# SCH.net
KiCad netlist of a schematic drawn in EasyEDA
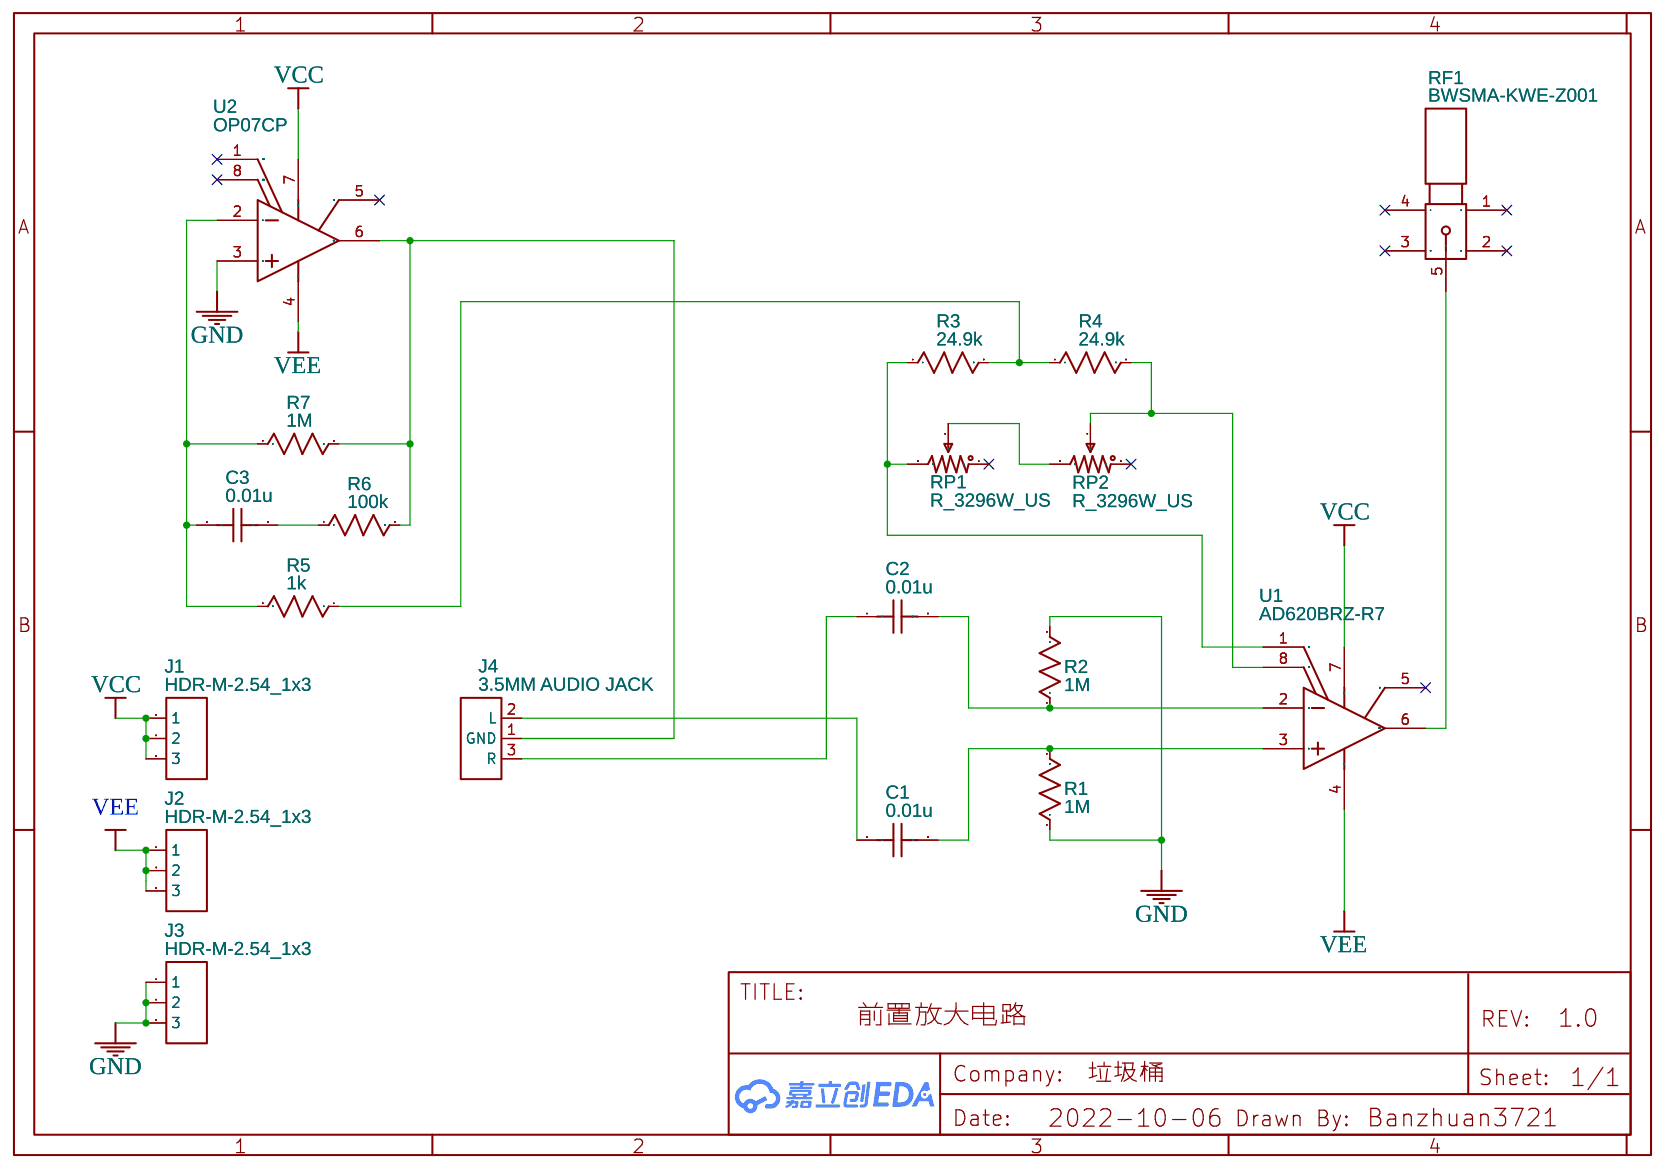
[diagram p0: schematic sheet]

(export (version "E")
  (design (tool "Eeschema 10.0.6"))
  (components
    (comp (ref "C1") (value "0.01u") (libsource (lib "") (part "C_RAD-0.2_US")))
    (comp (ref "C2") (value "0.01u") (libsource (lib "") (part "C_RAD-0.2_US")))
    (comp (ref "C3") (value "0.01u") (libsource (lib "") (part "C_RAD-0.2_US")))
    (comp (ref "J1")
      (value "HDR-M-2.54_1x3")
      (fields (field (name "BOM_Supplier Part") "C180248"))
      (libsource (lib "") (part "HDR-M-2.54_1x3"))
    )
    (comp (ref "J2")
      (value "HDR-M-2.54_1x3")
      (fields (field (name "BOM_Supplier Part") "C180248"))
      (libsource (lib "") (part "HDR-M-2.54_1x3"))
    )
    (comp (ref "J3")
      (value "HDR-M-2.54_1x3")
      (fields (field (name "BOM_Supplier Part") "C180248"))
      (libsource (lib "") (part "HDR-M-2.54_1x3"))
    )
    (comp (ref "J4")
      (value "3.5MM AUDIO JACK")
      (fields
        (field (name "BOM_Manufacturer Part") "PJ-325M/3.5MM")
        (field (name "BOM_Supplier Part") "C26230")
      )
      (libsource (lib "") (part "3.5MM AUDIO JACK"))
    )
    (comp (ref "R1") (value "1M") (libsource (lib "") (part "R_AXIAL-0.3_US_1")))
    (comp (ref "R2") (value "1M") (libsource (lib "") (part "R_AXIAL-0.3_US_1")))
    (comp (ref "R3") (value "24.9k") (libsource (lib "") (part "R_AXIAL-0.3_US")))
    (comp (ref "R4") (value "24.9k") (libsource (lib "") (part "R_AXIAL-0.3_US")))
    (comp (ref "R5") (value "1k") (libsource (lib "") (part "R_AXIAL-0.3_US_2")))
    (comp (ref "R6") (value "100k") (libsource (lib "") (part "R_AXIAL-0.3_US")))
    (comp (ref "R7") (value "1M") (libsource (lib "") (part "R_AXIAL-0.3_US")))
    (comp (ref "RF1")
      (value "BWSMA-KWE-Z001")
      (fields (field (name "BOM_Supplier Part") "C496551"))
      (libsource (lib "") (part "BWSMA-KWE-Z001"))
    )
    (comp (ref "RP1") (value "R_3296W_US") (libsource (lib "") (part "R_3296W_US")))
    (comp (ref "RP2") (value "R_3296W_US") (libsource (lib "") (part "R_3296W_US")))
    (comp (ref "U1")
      (value "AD620BRZ-R7")
      (fields (field (name "BOM_Supplier Part") "C392899"))
      (libsource (lib "") (part "AD620BRZ-R7"))
    )
    (comp (ref "U2")
      (value "OP07CP")
      (fields (field (name "BOM_Supplier Part") "C5224"))
      (libsource (lib "") (part "OP07CP"))
    )
  )
  (nets
    (net (code "1") (name "GND") (class "Default")
      (node (ref "J3") (pin "1") (pinfunction "1_1") (pintype "input"))
      (node (ref "J3") (pin "2") (pinfunction "2_2") (pintype "input"))
      (node (ref "J3") (pin "3") (pinfunction "3_3") (pintype "input"))
      (node (ref "R1") (pin "1") (pinfunction "1_1") (pintype "unspecified"))
      (node (ref "R2") (pin "2") (pinfunction "2_2") (pintype "unspecified"))
      (node (ref "U2") (pin "3") (pinfunction "IN+_3") (pintype "unspecified"))
    )
    (net (code "2") (name "Net-(C3-Pad2)") (class "Default")
      (node (ref "C3") (pin "2") (pinfunction "2_2") (pintype "unspecified"))
      (node (ref "R6") (pin "1") (pinfunction "1_1") (pintype "unspecified"))
    )
    (net (code "3") (name "Net-(J4-GND)") (class "Default")
      (node (ref "J4") (pin "1") (pinfunction "GND_1") (pintype "unspecified"))
      (node (ref "R6") (pin "2") (pinfunction "2_2") (pintype "unspecified"))
      (node (ref "R7") (pin "2") (pinfunction "2_2") (pintype "unspecified"))
      (node (ref "U2") (pin "6") (pinfunction "OUT_6") (pintype "output"))
    )
    (net (code "4") (name "Net-(J4-L)") (class "Default")
      (node (ref "C1") (pin "1") (pinfunction "1_1") (pintype "unspecified"))
      (node (ref "J4") (pin "2") (pinfunction "L_2") (pintype "unspecified"))
    )
    (net (code "5") (name "Net-(J4-R)") (class "Default")
      (node (ref "C2") (pin "1") (pinfunction "1_1") (pintype "unspecified"))
      (node (ref "J4") (pin "3") (pinfunction "R_3") (pintype "unspecified"))
    )
    (net (code "6") (name "Net-(R3-Pad1)") (class "Default")
      (node (ref "R3") (pin "1") (pinfunction "1_1") (pintype "unspecified"))
      (node (ref "RP1") (pin "3") (pinfunction "3_3") (pintype "unspecified"))
      (node (ref "U1") (pin "1") (pinfunction "RG_1") (pintype "unspecified"))
    )
    (net (code "7") (name "Net-(R3-Pad2)") (class "Default")
      (node (ref "R3") (pin "2") (pinfunction "2_2") (pintype "unspecified"))
      (node (ref "R4") (pin "1") (pinfunction "1_1") (pintype "unspecified"))
      (node (ref "R5") (pin "1") (pinfunction "1_1") (pintype "unspecified"))
    )
    (net (code "8") (name "Net-(R4-Pad2)") (class "Default")
      (node (ref "R4") (pin "2") (pinfunction "2_2") (pintype "unspecified"))
      (node (ref "RP2") (pin "2") (pinfunction "2_2") (pintype "unspecified"))
      (node (ref "U1") (pin "8") (pinfunction "RG_8") (pintype "unspecified"))
    )
    (net (code "9") (name "Net-(RP1-Pad2)") (class "Default")
      (node (ref "RP1") (pin "2") (pinfunction "2_2") (pintype "unspecified"))
      (node (ref "RP2") (pin "3") (pinfunction "3_3") (pintype "unspecified"))
    )
    (net (code "10") (name "Net-(U1-IN+)") (class "Default")
      (node (ref "C1") (pin "2") (pinfunction "2_2") (pintype "unspecified"))
      (node (ref "R1") (pin "2") (pinfunction "2_2") (pintype "unspecified"))
      (node (ref "U1") (pin "3") (pinfunction "IN+_3") (pintype "unspecified"))
    )
    (net (code "11") (name "Net-(U1-IN-)") (class "Default")
      (node (ref "C2") (pin "2") (pinfunction "2_2") (pintype "unspecified"))
      (node (ref "R2") (pin "1") (pinfunction "1_1") (pintype "unspecified"))
      (node (ref "U1") (pin "2") (pinfunction "IN-_2") (pintype "unspecified"))
    )
    (net (code "12") (name "Net-(U1-OUTPUT)") (class "Default")
      (node (ref "RF1") (pin "5") (pinfunction "5_5") (pintype "unspecified"))
      (node (ref "U1") (pin "6") (pinfunction "OUTPUT_6") (pintype "output"))
    )
    (net (code "13") (name "Net-(U2-IN-)") (class "Default")
      (node (ref "C3") (pin "1") (pinfunction "1_1") (pintype "unspecified"))
      (node (ref "R5") (pin "2") (pinfunction "2_2") (pintype "unspecified"))
      (node (ref "R7") (pin "1") (pinfunction "1_1") (pintype "unspecified"))
      (node (ref "U2") (pin "2") (pinfunction "IN-_2") (pintype "unspecified"))
    )
    (net (code "14") (name "VCC") (class "Default")
      (node (ref "J1") (pin "1") (pinfunction "1_1") (pintype "input"))
      (node (ref "J1") (pin "2") (pinfunction "2_2") (pintype "input"))
      (node (ref "J1") (pin "3") (pinfunction "3_3") (pintype "input"))
      (node (ref "U1") (pin "7") (pinfunction "+VS_7") (pintype "passive"))
      (node (ref "U2") (pin "7") (pinfunction "VCC+_7") (pintype "passive"))
    )
    (net (code "15") (name "VEE") (class "Default")
      (node (ref "J2") (pin "1") (pinfunction "1_1") (pintype "input"))
      (node (ref "J2") (pin "2") (pinfunction "2_2") (pintype "input"))
      (node (ref "J2") (pin "3") (pinfunction "3_3") (pintype "input"))
      (node (ref "U1") (pin "4") (pinfunction "-VS_4") (pintype "passive"))
      (node (ref "U2") (pin "4") (pinfunction "VCC-_4") (pintype "passive"))
    )
    (net (code "16") (name "unconnected-(RF1-Pad1)") (class "Default")
      (node (ref "RF1") (pin "1") (pinfunction "1_1") (pintype "unspecified+no_connect"))
    )
    (net (code "17") (name "unconnected-(RF1-Pad2)") (class "Default")
      (node (ref "RF1") (pin "2") (pinfunction "2_2") (pintype "unspecified+no_connect"))
    )
    (net (code "18") (name "unconnected-(RF1-Pad3)") (class "Default")
      (node (ref "RF1") (pin "3") (pinfunction "3_3") (pintype "unspecified+no_connect"))
    )
    (net (code "19") (name "unconnected-(RF1-Pad4)") (class "Default")
      (node (ref "RF1") (pin "4") (pinfunction "4_4") (pintype "unspecified+no_connect"))
    )
    (net (code "20") (name "unconnected-(RP1-Pad1)") (class "Default")
      (node (ref "RP1") (pin "1") (pinfunction "1_1") (pintype "unspecified+no_connect"))
    )
    (net (code "21") (name "unconnected-(RP2-Pad1)") (class "Default")
      (node (ref "RP2") (pin "1") (pinfunction "1_1") (pintype "unspecified+no_connect"))
    )
    (net (code "22") (name "unconnected-(U1-REF-Pad5)") (class "Default")
      (node (ref "U1") (pin "5") (pinfunction "REF_5") (pintype "unspecified+no_connect"))
    )
    (net (code "23") (name "unconnected-(U2-NC-Pad5)") (class "Default")
      (node (ref "U2") (pin "5") (pinfunction "NC_5") (pintype "unspecified+no_connect"))
    )
    (net (code "24") (name "unconnected-(U2-OFFSET_N1-Pad1)") (class "Default")
      (node (ref "U2") (pin "1") (pinfunction "OFFSET_N1_1") (pintype "unspecified+no_connect"))
    )
    (net (code "25") (name "unconnected-(U2-OFFSET_N2-Pad8)") (class "Default")
      (node (ref "U2") (pin "8") (pinfunction "OFFSET_N2_8") (pintype "unspecified+no_connect"))
    )
  )
)
